# Activities.net
KiCad netlist of a schematic drawn in EAGLE
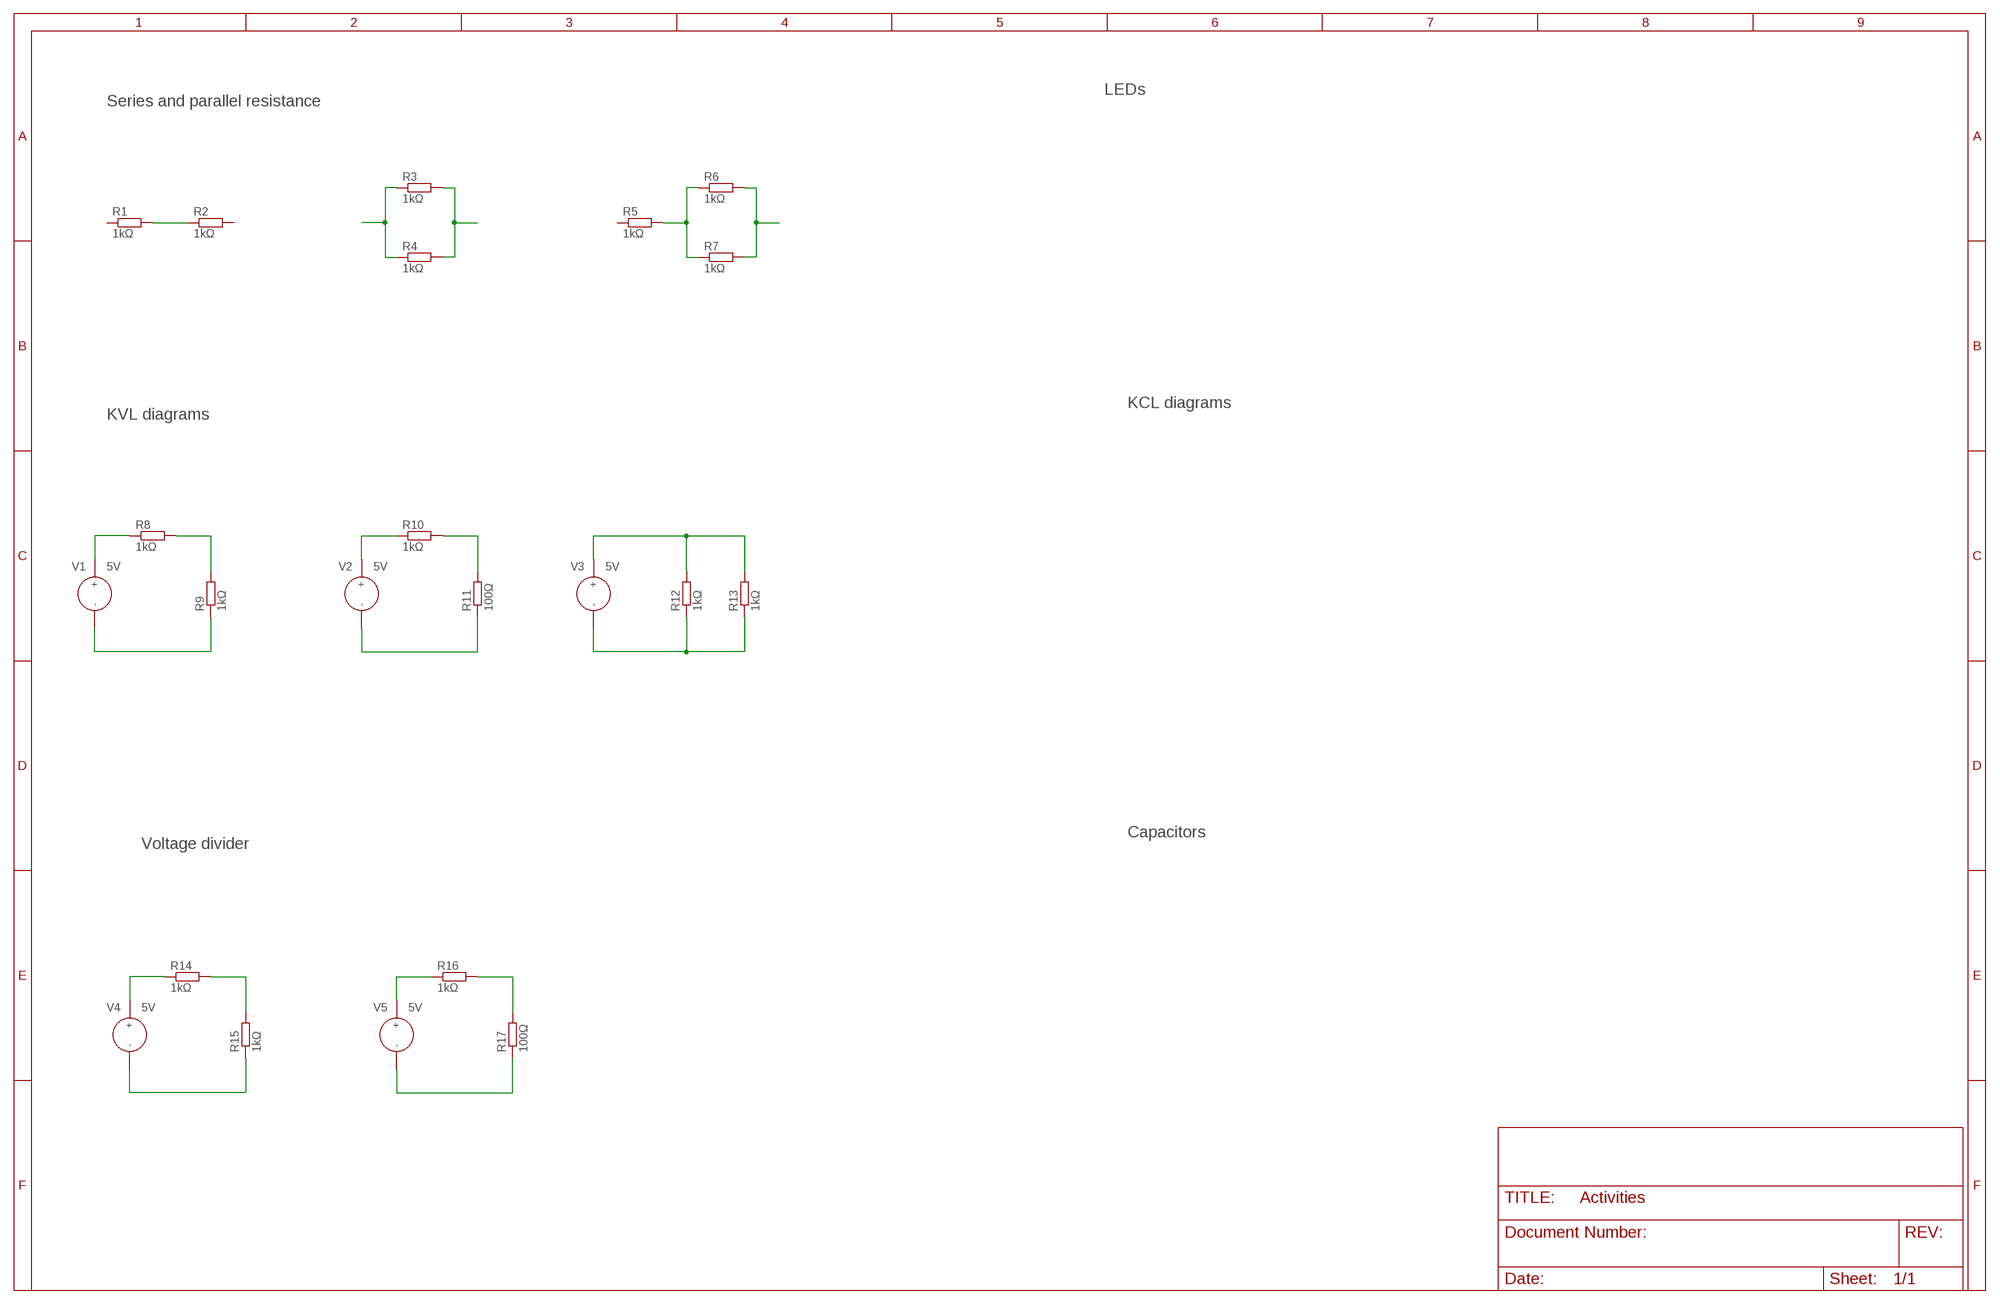
[diagram p0: schematic, sheet 1]

(export (version "E")
  (design (tool "Eeschema 10.0.6"))
  (components
    (comp (ref "R1")
      (value "1kΩ")
      (footprint "eagle-import:0207_10")
      (libsource (lib "eagle-import") (part "R-EU_0207/10"))
    )
    (comp (ref "R2")
      (value "1kΩ")
      (footprint "eagle-import:0207_10")
      (libsource (lib "eagle-import") (part "R-EU_0207/10"))
    )
    (comp (ref "R3")
      (value "1kΩ")
      (footprint "eagle-import:0207_10")
      (libsource (lib "eagle-import") (part "R-EU_0207/10"))
    )
    (comp (ref "R4")
      (value "1kΩ")
      (footprint "eagle-import:0207_10")
      (libsource (lib "eagle-import") (part "R-EU_0207/10"))
    )
    (comp (ref "R5")
      (value "1kΩ")
      (footprint "eagle-import:0207_10")
      (libsource (lib "eagle-import") (part "R-EU_0207/10"))
    )
    (comp (ref "R6")
      (value "1kΩ")
      (footprint "eagle-import:0207_10")
      (libsource (lib "eagle-import") (part "R-EU_0207/10"))
    )
    (comp (ref "R7")
      (value "1kΩ")
      (footprint "eagle-import:0207_10")
      (libsource (lib "eagle-import") (part "R-EU_0207/10"))
    )
    (comp (ref "R8")
      (value "1kΩ")
      (footprint "eagle-import:0207_10")
      (libsource (lib "eagle-import") (part "R-EU_0207/10"))
    )
    (comp (ref "R9")
      (value "1kΩ")
      (footprint "eagle-import:0207_10")
      (libsource (lib "eagle-import") (part "R-EU_0207/10"))
    )
    (comp (ref "R10")
      (value "1kΩ")
      (footprint "eagle-import:0207_10")
      (libsource (lib "eagle-import") (part "R-EU_0207/10"))
    )
    (comp (ref "R11")
      (value "100Ω")
      (footprint "eagle-import:0207_10")
      (libsource (lib "eagle-import") (part "R-EU_0207/10"))
    )
    (comp (ref "R12")
      (value "1kΩ")
      (footprint "eagle-import:0207_10")
      (libsource (lib "eagle-import") (part "R-EU_0207/10"))
    )
    (comp (ref "R13")
      (value "1kΩ")
      (footprint "eagle-import:0207_10")
      (libsource (lib "eagle-import") (part "R-EU_0207/10"))
    )
    (comp (ref "R14")
      (value "1kΩ")
      (footprint "eagle-import:0207_10")
      (libsource (lib "eagle-import") (part "R-EU_0207/10"))
    )
    (comp (ref "R15")
      (value "1kΩ")
      (footprint "eagle-import:0207_10")
      (libsource (lib "eagle-import") (part "R-EU_0207/10"))
    )
    (comp (ref "R16")
      (value "1kΩ")
      (footprint "eagle-import:0207_10")
      (libsource (lib "eagle-import") (part "R-EU_0207/10"))
    )
    (comp (ref "R17")
      (value "100Ω")
      (footprint "eagle-import:0207_10")
      (libsource (lib "eagle-import") (part "R-EU_0207/10"))
    )
    (comp (ref "V1")
      (value "5V")
      (footprint "eagle-import:VOLTAGE_SOURCE")
      (libsource (lib "eagle-import") (part "VOLTAGE_SOURCE"))
    )
    (comp (ref "V2")
      (value "5V")
      (footprint "eagle-import:VOLTAGE_SOURCE")
      (libsource (lib "eagle-import") (part "VOLTAGE_SOURCE"))
    )
    (comp (ref "V3")
      (value "5V")
      (footprint "eagle-import:VOLTAGE_SOURCE")
      (libsource (lib "eagle-import") (part "VOLTAGE_SOURCE"))
    )
    (comp (ref "V4")
      (value "5V")
      (footprint "eagle-import:VOLTAGE_SOURCE")
      (libsource (lib "eagle-import") (part "VOLTAGE_SOURCE"))
    )
    (comp (ref "V5")
      (value "5V")
      (footprint "eagle-import:VOLTAGE_SOURCE")
      (libsource (lib "eagle-import") (part "VOLTAGE_SOURCE"))
    )
  )
  (nets
    (net (code "1") (name "Net-(R1-Pad2)") (class "Default")
      (node (ref "R1") (pin "2") (pinfunction "2_2") (pintype "passive"))
      (node (ref "R2") (pin "1") (pinfunction "1_1") (pintype "passive"))
    )
    (net (code "2") (name "Net-(R3-Pad1)") (class "Default")
      (node (ref "R3") (pin "1") (pinfunction "1_1") (pintype "passive"))
      (node (ref "R4") (pin "1") (pinfunction "1_1") (pintype "passive"))
    )
    (net (code "3") (name "Net-(R3-Pad2)") (class "Default")
      (node (ref "R3") (pin "2") (pinfunction "2_2") (pintype "passive"))
      (node (ref "R4") (pin "2") (pinfunction "2_2") (pintype "passive"))
    )
    (net (code "4") (name "Net-(R5-Pad2)") (class "Default")
      (node (ref "R5") (pin "2") (pinfunction "2_2") (pintype "passive"))
      (node (ref "R6") (pin "1") (pinfunction "1_1") (pintype "passive"))
      (node (ref "R7") (pin "1") (pinfunction "1_1") (pintype "passive"))
    )
    (net (code "5") (name "Net-(R6-Pad2)") (class "Default")
      (node (ref "R6") (pin "2") (pinfunction "2_2") (pintype "passive"))
      (node (ref "R7") (pin "2") (pinfunction "2_2") (pintype "passive"))
    )
    (net (code "6") (name "Net-(R8-Pad2)") (class "Default")
      (node (ref "R8") (pin "2") (pinfunction "2_2") (pintype "passive"))
      (node (ref "R9") (pin "2") (pinfunction "2_2") (pintype "passive"))
    )
    (net (code "7") (name "Net-(R10-Pad2)") (class "Default")
      (node (ref "R10") (pin "2") (pinfunction "2_2") (pintype "passive"))
      (node (ref "R11") (pin "2") (pinfunction "2_2") (pintype "passive"))
    )
    (net (code "8") (name "Net-(R14-Pad2)") (class "Default")
      (node (ref "R14") (pin "2") (pinfunction "2_2") (pintype "passive"))
      (node (ref "R15") (pin "2") (pinfunction "2_2") (pintype "passive"))
    )
    (net (code "9") (name "Net-(R16-Pad2)") (class "Default")
      (node (ref "R16") (pin "2") (pinfunction "2_2") (pintype "passive"))
      (node (ref "R17") (pin "2") (pinfunction "2_2") (pintype "passive"))
    )
    (net (code "10") (name "Net-(V1-+)") (class "Default")
      (node (ref "R8") (pin "1") (pinfunction "1_1") (pintype "passive"))
      (node (ref "V1") (pin "1") (pinfunction "+_1") (pintype "bidirectional"))
    )
    (net (code "11") (name "Net-(V1--)") (class "Default")
      (node (ref "R9") (pin "1") (pinfunction "1_1") (pintype "passive"))
      (node (ref "V1") (pin "2") (pinfunction "-_2") (pintype "bidirectional"))
    )
    (net (code "12") (name "Net-(V2-+)") (class "Default")
      (node (ref "R10") (pin "1") (pinfunction "1_1") (pintype "passive"))
      (node (ref "V2") (pin "1") (pinfunction "+_1") (pintype "bidirectional"))
    )
    (net (code "13") (name "Net-(V2--)") (class "Default")
      (node (ref "R11") (pin "1") (pinfunction "1_1") (pintype "passive"))
      (node (ref "V2") (pin "2") (pinfunction "-_2") (pintype "bidirectional"))
    )
    (net (code "14") (name "Net-(V3-+)") (class "Default")
      (node (ref "R12") (pin "2") (pinfunction "2_2") (pintype "passive"))
      (node (ref "R13") (pin "2") (pinfunction "2_2") (pintype "passive"))
      (node (ref "V3") (pin "1") (pinfunction "+_1") (pintype "bidirectional"))
    )
    (net (code "15") (name "Net-(V3--)") (class "Default")
      (node (ref "R12") (pin "1") (pinfunction "1_1") (pintype "passive"))
      (node (ref "R13") (pin "1") (pinfunction "1_1") (pintype "passive"))
      (node (ref "V3") (pin "2") (pinfunction "-_2") (pintype "bidirectional"))
    )
    (net (code "16") (name "Net-(V4-+)") (class "Default")
      (node (ref "R14") (pin "1") (pinfunction "1_1") (pintype "passive"))
      (node (ref "V4") (pin "1") (pinfunction "+_1") (pintype "bidirectional"))
    )
    (net (code "17") (name "Net-(V4--)") (class "Default")
      (node (ref "R15") (pin "1") (pinfunction "1_1") (pintype "passive"))
      (node (ref "V4") (pin "2") (pinfunction "-_2") (pintype "bidirectional"))
    )
    (net (code "18") (name "Net-(V5-+)") (class "Default")
      (node (ref "R16") (pin "1") (pinfunction "1_1") (pintype "passive"))
      (node (ref "V5") (pin "1") (pinfunction "+_1") (pintype "bidirectional"))
    )
    (net (code "19") (name "Net-(V5--)") (class "Default")
      (node (ref "R17") (pin "1") (pinfunction "1_1") (pintype "passive"))
      (node (ref "V5") (pin "2") (pinfunction "-_2") (pintype "bidirectional"))
    )
    (net (code "20") (name "unconnected-(R1-Pad1)") (class "Default")
      (node (ref "R1") (pin "1") (pinfunction "1_1") (pintype "passive"))
    )
    (net (code "21") (name "unconnected-(R2-Pad2)") (class "Default")
      (node (ref "R2") (pin "2") (pinfunction "2_2") (pintype "passive"))
    )
    (net (code "22") (name "unconnected-(R5-Pad1)") (class "Default")
      (node (ref "R5") (pin "1") (pinfunction "1_1") (pintype "passive"))
    )
  )
)
